# DC_DC.net
KiCad netlist of a schematic drawn in Altium Designer
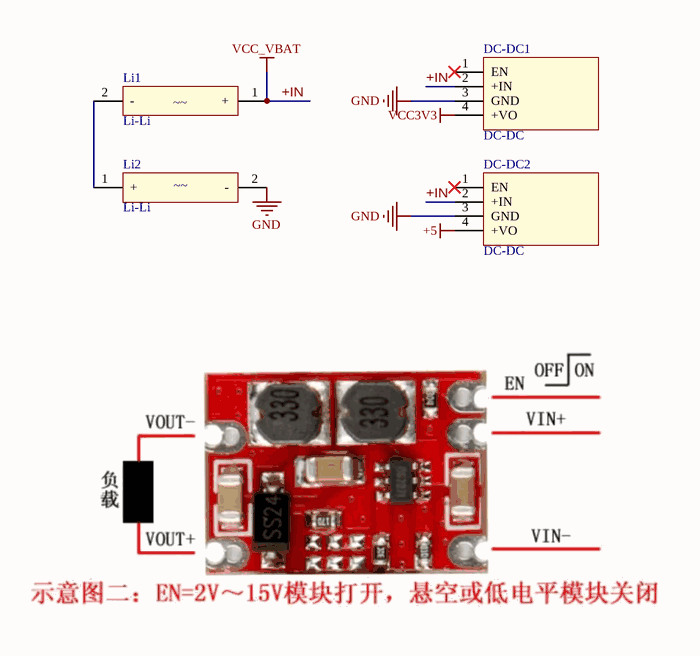
[diagram p0: DC_DC.SchDoc]

(export (version "E")
  (design (tool "Eeschema 10.0.6"))
  (components
    (comp (ref "DC-DC1") (value "DC-DC") (footprint "DC-DC") (libsource (lib "STM32_Phone") (part "DC-DC")))
    (comp (ref "DC-DC2") (value "DC-DC") (footprint "DC-DC") (libsource (lib "STM32_Phone") (part "DC-DC")))
    (comp (ref "Li1") (value "Li-Li") (footprint "单个5号电池盒") (libsource (lib "STM32_Phone") (part "Li-Li")))
    (comp (ref "Li2") (value "Li-Li") (footprint "单个5号电池盒") (libsource (lib "") (part "Li-Li_1")))
  )
  (nets
    (net (code "1") (name "+5") (class "Default")
      (node (ref "DC-DC2") (pin "4") (pinfunction "+VO_4") (pintype "passive"))
    )
    (net (code "2") (name "GND") (class "Default")
      (node (ref "DC-DC1") (pin "3") (pinfunction "GND_3") (pintype "passive"))
      (node (ref "DC-DC2") (pin "3") (pinfunction "GND_3") (pintype "passive"))
      (node (ref "Li2") (pin "2") (pinfunction "-_2") (pintype "passive"))
    )
    (net (code "3") (name "Net-(Li1--)") (class "Default")
      (node (ref "Li1") (pin "2") (pinfunction "-_2") (pintype "passive"))
      (node (ref "Li2") (pin "1") (pinfunction "+_1") (pintype "passive"))
    )
    (net (code "4") (name "VCC3V3") (class "Default")
      (node (ref "DC-DC1") (pin "4") (pinfunction "+VO_4") (pintype "passive"))
    )
    (net (code "5") (name "VCC_VBAT") (class "Default")
      (node (ref "DC-DC1") (pin "2") (pinfunction "+IN_2") (pintype "passive"))
      (node (ref "DC-DC2") (pin "2") (pinfunction "+IN_2") (pintype "passive"))
      (node (ref "Li1") (pin "1") (pinfunction "+_1") (pintype "passive"))
    )
    (net (code "6") (name "unconnected-(DC-DC1-EN-Pad1)") (class "Default")
      (node (ref "DC-DC1") (pin "1") (pinfunction "EN_1") (pintype "passive+no_connect"))
    )
    (net (code "7") (name "unconnected-(DC-DC2-EN-Pad1)") (class "Default")
      (node (ref "DC-DC2") (pin "1") (pinfunction "EN_1") (pintype "passive+no_connect"))
    )
  )
)
